# 3V-Switcher-50mA.net
KiCad netlist of a schematic drawn in Altium Designer
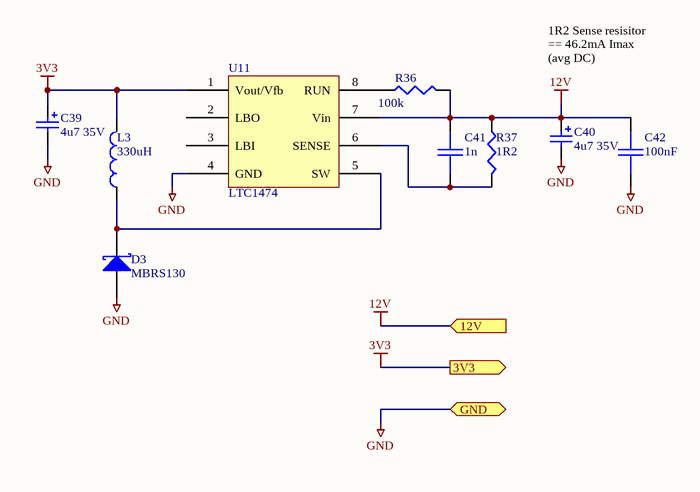
[diagram p0: 3V-Switcher-50mA.SCHDOC]

(export (version "E")
  (design (tool "Eeschema 10.0.6"))
  (components
    (comp (ref "C39")
      (value "4u7 35V")
      (footprint "MCCT-CASEC")
      (description "Polarized Capacitor (Surface Mount)")
      (libsource (lib "Miscellaneous Devices") (part "Cap Pol3"))
    )
    (comp (ref "C40")
      (value "4u7 35V")
      (footprint "MCCT-CASEC")
      (description "Polarized Capacitor (Surface Mount)")
      (libsource (lib "Miscellaneous Devices") (part "Cap Pol3"))
    )
    (comp (ref "C41")
      (value "1n")
      (footprint "0603")
      (description "Capacitor")
      (libsource (lib "Miscellaneous Devices") (part "CAP"))
    )
    (comp (ref "C42")
      (value "100nF")
      (footprint "0603")
      (description "Capacitor")
      (libsource (lib "Miscellaneous Devices") (part "CAP"))
    )
    (comp (ref "D3")
      (value "MBRS130")
      (footprint "SMB")
      (description "Schottky Diode")
      (libsource (lib "RCLDQ") (part "D SCHOTTKY"))
    )
    (comp (ref "L3")
      (value "330uH")
      (footprint "1812")
      (description "Inductor")
      (libsource (lib "Miscellaneous Devices") (part "Inductor"))
    )
    (comp (ref "R36")
      (value "100k")
      (footprint "0603")
      (description "Resistor")
      (libsource (lib "RCLDQ") (part "RES1"))
    )
    (comp (ref "R37")
      (value "1R2")
      (footprint "0603")
      (description "Resistor")
      (libsource (lib "Miscellaneous Devices") (part "RES1"))
    )
    (comp (ref "U11")
      (value "LTC1474")
      (footprint "TSOP8")
      (description "Step-down converter")
      (libsource (lib "MiscellaneousIC") (part "LTC1474"))
    )
  )
  (nets
    (net (code "1") (name "3V3") (class "Default")
      (node (ref "C39") (pin "1") (pinfunction "1_1") (pintype "passive"))
      (node (ref "L3") (pin "2") (pinfunction "2_2") (pintype "passive"))
      (node (ref "U11") (pin "1") (pinfunction "Vout/Vfb_1") (pintype "passive"))
    )
    (net (code "2") (name "12V") (class "Default")
      (node (ref "C40") (pin "1") (pinfunction "1_1") (pintype "passive"))
      (node (ref "C41") (pin "1") (pinfunction "1_1") (pintype "passive"))
      (node (ref "C42") (pin "1") (pinfunction "1_1") (pintype "passive"))
      (node (ref "R36") (pin "2") (pinfunction "2_2") (pintype "passive"))
      (node (ref "R37") (pin "1") (pinfunction "1_1") (pintype "passive"))
      (node (ref "U11") (pin "7") (pinfunction "Vin_7") (pintype "passive"))
    )
    (net (code "3") (name "GND") (class "Default")
      (node (ref "C39") (pin "2") (pinfunction "2_2") (pintype "passive"))
      (node (ref "C40") (pin "2") (pinfunction "2_2") (pintype "passive"))
      (node (ref "C42") (pin "2") (pinfunction "2_2") (pintype "passive"))
      (node (ref "D3") (pin "A") (pinfunction "A_A") (pintype "passive"))
      (node (ref "U11") (pin "4") (pinfunction "GND_4") (pintype "passive"))
    )
    (net (code "4") (name "Net-(U11-RUN)") (class "Default")
      (node (ref "R36") (pin "1") (pinfunction "1_1") (pintype "passive"))
      (node (ref "U11") (pin "8") (pinfunction "RUN_8") (pintype "passive"))
    )
    (net (code "5") (name "Net-(U11-SENSE)") (class "Default")
      (node (ref "C41") (pin "2") (pinfunction "2_2") (pintype "passive"))
      (node (ref "R37") (pin "2") (pinfunction "2_2") (pintype "passive"))
      (node (ref "U11") (pin "6") (pinfunction "SENSE_6") (pintype "passive"))
    )
    (net (code "6") (name "Net-(U11-SW)") (class "Default")
      (node (ref "D3") (pin "K") (pinfunction "K_K") (pintype "passive"))
      (node (ref "L3") (pin "1") (pinfunction "1_1") (pintype "passive"))
      (node (ref "U11") (pin "5") (pinfunction "SW_5") (pintype "passive"))
    )
    (net (code "7") (name "unconnected-(U11-LBI-Pad3)") (class "Default")
      (node (ref "U11") (pin "3") (pinfunction "LBI_3") (pintype "passive"))
    )
    (net (code "8") (name "unconnected-(U11-LBO-Pad2)") (class "Default")
      (node (ref "U11") (pin "2") (pinfunction "LBO_2") (pintype "passive"))
    )
  )
)
